# MiiScoreBoard.net
KiCad netlist of a schematic drawn in EAGLE
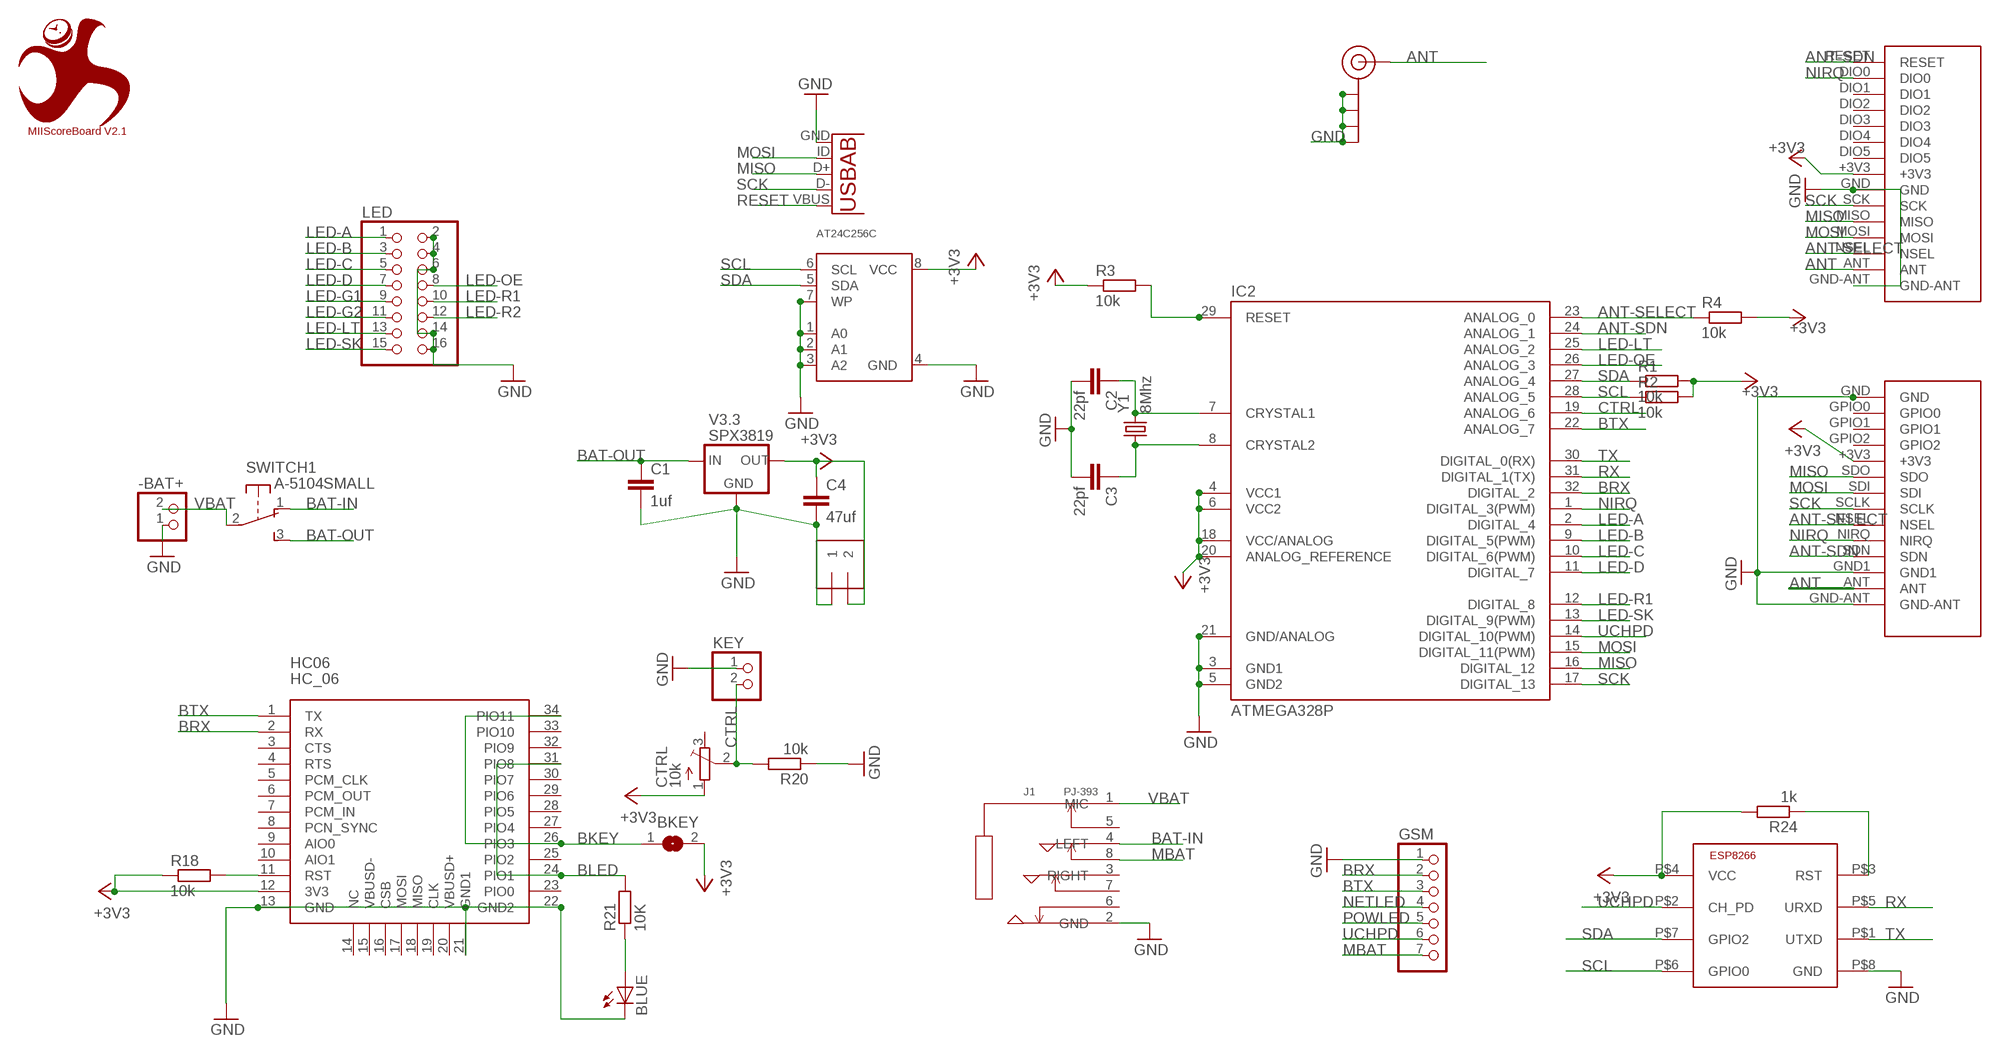
[diagram p0: schematic, sheet 1]

(export (version "E")
  (design (tool "Eeschema 10.0.6"))
  (components
    (comp (ref "-BAT+")
      (value "JST_2PIN-THM")
      (footprint "eagle-import:JST-PH-2-THM")
      (libsource (lib "eagle-import") (part "JST_2PIN-THM"))
    )
    (comp (ref "-LED+")
      (value "-BAT+")
      (footprint "eagle-import:1X2-3.5MM")
      (libsource (lib "eagle-import") (part "1X2-3.5MM"))
    )
    (comp (ref "AT24C256C")
      (value "EEPROM_I2C_SOIC8_GENERIC")
      (footprint "eagle-import:SOIC8_150MIL")
      (libsource (lib "eagle-import") (part "EEPROM_I2C_SOIC8_GENERIC"))
    )
    (comp (ref "BKEY")
      (value "SOLDERJUMPER")
      (footprint "eagle-import:SOLDERJUMPER_ARROW_NOPASTE")
      (libsource (lib "eagle-import") (part "SOLDERJUMPER"))
    )
    (comp (ref "BLUE")
      (value "LEDCHIP-LED0805")
      (footprint "eagle-import:CHIP-LED0805")
      (libsource (lib "eagle-import") (part "LEDCHIP-LED0805"))
    )
    (comp (ref "C1")
      (value "1uf")
      (footprint "eagle-import:C0805")
      (libsource (lib "eagle-import") (part "C-EUC0805"))
    )
    (comp (ref "C2")
      (value "22pf")
      (footprint "eagle-import:C0805")
      (libsource (lib "eagle-import") (part "C-EUC0805"))
    )
    (comp (ref "C3")
      (value "22pf")
      (footprint "eagle-import:C0805")
      (libsource (lib "eagle-import") (part "C-EUC0805"))
    )
    (comp (ref "C4")
      (value "47uf")
      (footprint "eagle-import:C0805")
      (libsource (lib "eagle-import") (part "C-EUC0805"))
    )
    (comp (ref "CTRL")
      (value "10k")
      (footprint "eagle-import:TC33X")
      (libsource (lib "eagle-import") (part "TRIMPOTTC33X"))
    )
    (comp (ref "GSM")
      (value "PINHD-1X07_2.54")
      (footprint "eagle-import:1X07")
      (libsource (lib "eagle-import") (part "PINHD-1X07_2.54"))
    )
    (comp (ref "HC06")
      (value "HC_06")
      (footprint "eagle-import:BLUETOOTH_SMD")
      (libsource (lib "eagle-import") (part "HC_05"))
    )
    (comp (ref "IC2")
      (value "ATMEGA328P")
      (footprint "eagle-import:TQFP32-08")
      (libsource (lib "eagle-import") (part "ATMEGA168-AU"))
    )
    (comp (ref "ISP1")
      (value "USB-ABUSB_SIERK")
      (footprint "eagle-import:USB_AB_MICRO_SJH")
      (libsource (lib "eagle-import") (part "USB-ABUSB_SIERK"))
    )
    (comp (ref "J$1")
      (value "SMA_EDGE")
      (footprint "eagle-import:SMA-EDGE")
      (libsource (lib "eagle-import") (part "SMA_EDGE"))
    )
    (comp (ref "J1")
      (value "PJ-393")
      (footprint "eagle-import:AUDIO8P-SMD-3.5-14.5X6.1X4.0MM")
      (libsource (lib "eagle-import") (part "AUDIO-JACK-PJ-393(8P-SMD)"))
    )
    (comp (ref "KEY")
      (value "PINHD-1X02_2.54-90°")
      (footprint "eagle-import:1X02_90")
      (libsource (lib "eagle-import") (part "PINHD-1X02_2.54-90°"))
    )
    (comp (ref "LED")
      (value "PINHD-2X08_2.54")
      (footprint "eagle-import:2X08")
      (libsource (lib "eagle-import") (part "PINHD-2X08_2.54"))
    )
    (comp (ref "R1")
      (value "10k")
      (footprint "eagle-import:R0805")
      (libsource (lib "eagle-import") (part "R-EU_R0805"))
    )
    (comp (ref "R2")
      (value "10k")
      (footprint "eagle-import:R0805")
      (libsource (lib "eagle-import") (part "R-EU_R0805"))
    )
    (comp (ref "R3")
      (value "10k")
      (footprint "eagle-import:R0805")
      (libsource (lib "eagle-import") (part "R-EU_R0805"))
    )
    (comp (ref "R4")
      (value "10k")
      (footprint "eagle-import:R0805")
      (libsource (lib "eagle-import") (part "R-EU_R0805"))
    )
    (comp (ref "R18")
      (value "10k")
      (footprint "eagle-import:R0805")
      (libsource (lib "eagle-import") (part "R-EU_R0805"))
    )
    (comp (ref "R20")
      (value "10k")
      (footprint "eagle-import:R0805")
      (libsource (lib "eagle-import") (part "R-EU_R0805"))
    )
    (comp (ref "R21")
      (value "10K")
      (footprint "eagle-import:R0805")
      (libsource (lib "eagle-import") (part "R-EU_R0805"))
    )
    (comp (ref "R24")
      (value "1k")
      (footprint "eagle-import:R0805")
      (libsource (lib "eagle-import") (part "R-EU_R0805"))
    )
    (comp (ref "SWITCH")
      (value "A-5104SMALL")
      (footprint "eagle-import:A-5104-SMALL")
      (libsource (lib "eagle-import") (part "A-5104SMALL"))
    )
    (comp (ref "U$1")
      (value "MIIScoreBoard V2.1")
      (footprint "eagle-import:MIICHRONO")
      (libsource (lib "eagle-import") (part "MIICHRONO"))
    )
    (comp (ref "U$2")
      (value "DRF1278F")
      (footprint "eagle-import:DRF1278F")
      (libsource (lib "eagle-import") (part "DRF1278F"))
    )
    (comp (ref "U$6")
      (value "ESP8266-01")
      (footprint "eagle-import:ESP-01")
      (libsource (lib "eagle-import") (part "ESP8266-01"))
    )
    (comp (ref "U$7")
      (value "SI4432")
      (footprint "eagle-import:SI4432")
      (libsource (lib "eagle-import") (part "SPI4432"))
    )
    (comp (ref "V3.3")
      (value "SPX3819")
      (footprint "eagle-import:SOT23-5")
      (libsource (lib "eagle-import") (part "SPX3819"))
    )
    (comp (ref "Y1")
      (value "8Mhz")
      (footprint "eagle-import:HC49UP")
      (libsource (lib "eagle-import") (part "CRYSTALSMD"))
    )
  )
  (nets
    (net (code "1") (name "+3V3") (class "Default")
      (node (ref "-LED+") (pin "2") (pinfunction "2_2") (pintype "passive"))
      (node (ref "AT24C256C") (pin "8") (pinfunction "VCC_8") (pintype "power_in"))
      (node (ref "BKEY") (pin "2") (pinfunction "2_2") (pintype "passive"))
      (node (ref "C4") (pin "1") (pinfunction "1_1") (pintype "passive"))
      (node (ref "CTRL") (pin "1") (pinfunction "A_1") (pintype "passive"))
      (node (ref "HC06") (pin "12") (pinfunction "3V3_12") (pintype "bidirectional"))
      (node (ref "IC2") (pin "18") (pinfunction "VCC/ANALOG_18") (pintype "passive"))
      (node (ref "IC2") (pin "20") (pinfunction "ANALOG_REFERENCE_20") (pintype "passive"))
      (node (ref "IC2") (pin "4") (pinfunction "VCC1_4") (pintype "power_in"))
      (node (ref "IC2") (pin "6") (pinfunction "VCC2_6") (pintype "power_in"))
      (node (ref "R1") (pin "2") (pinfunction "2_2") (pintype "passive"))
      (node (ref "R18") (pin "1") (pinfunction "1_1") (pintype "passive"))
      (node (ref "R2") (pin "2") (pinfunction "2_2") (pintype "passive"))
      (node (ref "R24") (pin "2") (pinfunction "2_2") (pintype "passive"))
      (node (ref "R3") (pin "1") (pinfunction "1_1") (pintype "passive"))
      (node (ref "R4") (pin "2") (pinfunction "2_2") (pintype "passive"))
      (node (ref "U$2") (pin "+3V3") (pinfunction "+3V3_+3V3") (pintype "bidirectional"))
      (node (ref "U$6") (pin "P$4") (pinfunction "VCC_P$4") (pintype "bidirectional"))
      (node (ref "U$7") (pin "+3V3") (pinfunction "+3V3_+3V3") (pintype "bidirectional"))
      (node (ref "V3.3") (pin "5") (pinfunction "OUT_5") (pintype "output"))
    )
    (net (code "2") (name "/ANT") (class "Default")
      (node (ref "J$1") (pin "$P1") (pinfunction "SIGNAL_$P1") (pintype "bidirectional"))
      (node (ref "U$2") (pin "ANT") (pinfunction "ANT_ANT") (pintype "bidirectional"))
      (node (ref "U$7") (pin "ANT") (pinfunction "ANT_ANT") (pintype "bidirectional"))
    )
    (net (code "3") (name "/ANT-SDN") (class "Default")
      (node (ref "IC2") (pin "24") (pinfunction "ANALOG_1_24") (pintype "bidirectional"))
      (node (ref "U$2") (pin "RESET") (pinfunction "RESET_RESET") (pintype "bidirectional"))
      (node (ref "U$7") (pin "SDN") (pinfunction "SDN_SDN") (pintype "bidirectional"))
    )
    (net (code "4") (name "/ANT-SELECT") (class "Default")
      (node (ref "IC2") (pin "23") (pinfunction "ANALOG_0_23") (pintype "bidirectional"))
      (node (ref "R4") (pin "1") (pinfunction "1_1") (pintype "passive"))
      (node (ref "U$2") (pin "NSEL") (pinfunction "NSEL_NSEL") (pintype "bidirectional"))
      (node (ref "U$7") (pin "NSEL") (pinfunction "NSEL_NSEL") (pintype "bidirectional"))
    )
    (net (code "5") (name "/BAT-IN") (class "Default")
      (node (ref "J1") (pin "4") (pinfunction "LEFT_4") (pintype "bidirectional"))
      (node (ref "SWITCH") (pin "1") (pinfunction "O_1") (pintype "passive"))
    )
    (net (code "6") (name "/BAT-OUT") (class "Default")
      (node (ref "C1") (pin "1") (pinfunction "1_1") (pintype "passive"))
      (node (ref "SWITCH") (pin "3") (pinfunction "S_3") (pintype "passive"))
      (node (ref "V3.3") (pin "1") (pinfunction "IN_1") (pintype "input"))
      (node (ref "V3.3") (pin "3") (pinfunction "IN_3") (pintype "input"))
    )
    (net (code "7") (name "/BKEY") (class "Default")
      (node (ref "BKEY") (pin "1") (pinfunction "1_1") (pintype "passive"))
      (node (ref "HC06") (pin "26") (pinfunction "PIO3_26") (pintype "bidirectional"))
      (node (ref "HC06") (pin "34") (pinfunction "PIO11_34") (pintype "bidirectional"))
    )
    (net (code "8") (name "/BLED") (class "Default")
      (node (ref "HC06") (pin "24") (pinfunction "PIO1_24") (pintype "bidirectional"))
      (node (ref "HC06") (pin "31") (pinfunction "PIO8_31") (pintype "bidirectional"))
      (node (ref "R21") (pin "2") (pinfunction "2_2") (pintype "passive"))
    )
    (net (code "9") (name "/BRX") (class "Default")
      (node (ref "GSM") (pin "2") (pinfunction "2_2") (pintype "passive"))
      (node (ref "HC06") (pin "2") (pinfunction "RX_2") (pintype "bidirectional"))
      (node (ref "IC2") (pin "32") (pinfunction "DIGITAL_2_32") (pintype "bidirectional"))
    )
    (net (code "10") (name "/BTX") (class "Default")
      (node (ref "GSM") (pin "3") (pinfunction "3_3") (pintype "passive"))
      (node (ref "HC06") (pin "1") (pinfunction "TX_1") (pintype "bidirectional"))
      (node (ref "IC2") (pin "22") (pinfunction "ANALOG_7_22") (pintype "passive"))
    )
    (net (code "11") (name "/CTRL") (class "Default")
      (node (ref "CTRL") (pin "2") (pinfunction "S_2") (pintype "passive"))
      (node (ref "IC2") (pin "19") (pinfunction "ANALOG_6_19") (pintype "passive"))
      (node (ref "KEY") (pin "2") (pinfunction "2_2") (pintype "passive"))
      (node (ref "R20") (pin "2") (pinfunction "2_2") (pintype "passive"))
    )
    (net (code "12") (name "/LED-A") (class "Default")
      (node (ref "IC2") (pin "2") (pinfunction "DIGITAL_4_2") (pintype "bidirectional"))
      (node (ref "LED") (pin "1") (pinfunction "1_1") (pintype "passive"))
    )
    (net (code "13") (name "/LED-B") (class "Default")
      (node (ref "IC2") (pin "9") (pinfunction "DIGITAL_5(PWM)_9") (pintype "bidirectional"))
      (node (ref "LED") (pin "3") (pinfunction "3_3") (pintype "passive"))
    )
    (net (code "14") (name "/LED-C") (class "Default")
      (node (ref "IC2") (pin "10") (pinfunction "DIGITAL_6(PWM)_10") (pintype "bidirectional"))
      (node (ref "LED") (pin "5") (pinfunction "5_5") (pintype "passive"))
    )
    (net (code "15") (name "/LED-D") (class "Default")
      (node (ref "IC2") (pin "11") (pinfunction "DIGITAL_7_11") (pintype "bidirectional"))
      (node (ref "LED") (pin "7") (pinfunction "7_7") (pintype "passive"))
    )
    (net (code "16") (name "/LED-G1") (class "Default")
      (node (ref "LED") (pin "9") (pinfunction "9_9") (pintype "passive"))
    )
    (net (code "17") (name "/LED-G2") (class "Default")
      (node (ref "LED") (pin "11") (pinfunction "11_11") (pintype "passive"))
    )
    (net (code "18") (name "/LED-LT") (class "Default")
      (node (ref "IC2") (pin "25") (pinfunction "ANALOG_2_25") (pintype "bidirectional"))
      (node (ref "LED") (pin "13") (pinfunction "13_13") (pintype "passive"))
    )
    (net (code "19") (name "/LED-OE") (class "Default")
      (node (ref "IC2") (pin "26") (pinfunction "ANALOG_3_26") (pintype "bidirectional"))
      (node (ref "LED") (pin "8") (pinfunction "8_8") (pintype "passive"))
    )
    (net (code "20") (name "/LED-R1") (class "Default")
      (node (ref "IC2") (pin "12") (pinfunction "DIGITAL_8_12") (pintype "bidirectional"))
      (node (ref "LED") (pin "10") (pinfunction "10_10") (pintype "passive"))
    )
    (net (code "21") (name "/LED-R2") (class "Default")
      (node (ref "LED") (pin "12") (pinfunction "12_12") (pintype "passive"))
    )
    (net (code "22") (name "/LED-SK") (class "Default")
      (node (ref "IC2") (pin "13") (pinfunction "DIGITAL_9(PWM)_13") (pintype "bidirectional"))
      (node (ref "LED") (pin "15") (pinfunction "15_15") (pintype "passive"))
    )
    (net (code "23") (name "/MBAT") (class "Default")
      (node (ref "GSM") (pin "7") (pinfunction "7_7") (pintype "passive"))
      (node (ref "J1") (pin "8") (pinfunction "8_8") (pintype "bidirectional"))
    )
    (net (code "24") (name "/MISO") (class "Default")
      (node (ref "IC2") (pin "16") (pinfunction "DIGITAL_12_16") (pintype "bidirectional"))
      (node (ref "ISP1") (pin "D+") (pinfunction "D+_D+") (pintype "bidirectional"))
      (node (ref "U$2") (pin "MISO") (pinfunction "MISO_MISO") (pintype "bidirectional"))
      (node (ref "U$7") (pin "SDO") (pinfunction "SDO_SDO") (pintype "bidirectional"))
    )
    (net (code "25") (name "/MOSI") (class "Default")
      (node (ref "IC2") (pin "15") (pinfunction "DIGITAL_11(PWM)_15") (pintype "bidirectional"))
      (node (ref "ISP1") (pin "ID") (pinfunction "USBID_ID") (pintype "bidirectional"))
      (node (ref "U$2") (pin "MOSI") (pinfunction "MOSI_MOSI") (pintype "bidirectional"))
      (node (ref "U$7") (pin "SDI") (pinfunction "SDI_SDI") (pintype "bidirectional"))
    )
    (net (code "26") (name "/NETLED") (class "Default")
      (node (ref "GSM") (pin "4") (pinfunction "4_4") (pintype "passive"))
    )
    (net (code "27") (name "/NIRQ") (class "Default")
      (node (ref "IC2") (pin "1") (pinfunction "DIGITAL_3(PWM)_1") (pintype "bidirectional"))
      (node (ref "U$2") (pin "DIO0") (pinfunction "DIO0_DIO0") (pintype "bidirectional"))
      (node (ref "U$7") (pin "NIRQ") (pinfunction "NIRQ_NIRQ") (pintype "bidirectional"))
    )
    (net (code "28") (name "/POWLED") (class "Default")
      (node (ref "GSM") (pin "5") (pinfunction "5_5") (pintype "passive"))
    )
    (net (code "29") (name "/RESET") (class "Default")
      (node (ref "IC2") (pin "29") (pinfunction "RESET_29") (pintype "bidirectional"))
      (node (ref "ISP1") (pin "VBUS") (pinfunction "VBUS_VBUS") (pintype "bidirectional"))
      (node (ref "R3") (pin "2") (pinfunction "2_2") (pintype "passive"))
    )
    (net (code "30") (name "/RX") (class "Default")
      (node (ref "IC2") (pin "31") (pinfunction "DIGITAL_1(TX)_31") (pintype "bidirectional"))
      (node (ref "U$6") (pin "P$5") (pinfunction "URXD_P$5") (pintype "bidirectional"))
    )
    (net (code "31") (name "/SCK") (class "Default")
      (node (ref "IC2") (pin "17") (pinfunction "DIGITAL_13_17") (pintype "bidirectional"))
      (node (ref "ISP1") (pin "D-") (pinfunction "D-_D-") (pintype "bidirectional"))
      (node (ref "U$2") (pin "SCK") (pinfunction "SCK_SCK") (pintype "bidirectional"))
      (node (ref "U$7") (pin "SCLK") (pinfunction "SCLK_SCLK") (pintype "bidirectional"))
    )
    (net (code "32") (name "/SCL") (class "Default")
      (node (ref "AT24C256C") (pin "6") (pinfunction "SCL_6") (pintype "input"))
      (node (ref "IC2") (pin "28") (pinfunction "ANALOG_5_28") (pintype "bidirectional"))
      (node (ref "R2") (pin "1") (pinfunction "1_1") (pintype "passive"))
      (node (ref "U$6") (pin "P$6") (pinfunction "GPIO0_P$6") (pintype "bidirectional"))
    )
    (net (code "33") (name "/SDA") (class "Default")
      (node (ref "AT24C256C") (pin "5") (pinfunction "SDA_5") (pintype "bidirectional"))
      (node (ref "IC2") (pin "27") (pinfunction "ANALOG_4_27") (pintype "bidirectional"))
      (node (ref "R1") (pin "1") (pinfunction "1_1") (pintype "passive"))
      (node (ref "U$6") (pin "P$7") (pinfunction "GPIO2_P$7") (pintype "bidirectional"))
    )
    (net (code "34") (name "/TX") (class "Default")
      (node (ref "IC2") (pin "30") (pinfunction "DIGITAL_0(RX)_30") (pintype "bidirectional"))
      (node (ref "U$6") (pin "P$1") (pinfunction "UTXD_P$1") (pintype "bidirectional"))
    )
    (net (code "35") (name "/UCHPD") (class "Default")
      (node (ref "GSM") (pin "6") (pinfunction "6_6") (pintype "passive"))
      (node (ref "IC2") (pin "14") (pinfunction "DIGITAL_10(PWM)_14") (pintype "bidirectional"))
      (node (ref "U$6") (pin "P$2") (pinfunction "CH_PD_P$2") (pintype "bidirectional"))
    )
    (net (code "36") (name "/VBAT") (class "Default")
      (node (ref "-BAT+") (pin "2") (pinfunction "1_2") (pintype "passive"))
      (node (ref "J1") (pin "1") (pinfunction "MIC_1") (pintype "bidirectional"))
      (node (ref "SWITCH") (pin "2") (pinfunction "P_2") (pintype "passive"))
    )
    (net (code "37") (name "GND") (class "Default")
      (node (ref "-BAT+") (pin "1") (pinfunction "2_1") (pintype "passive"))
      (node (ref "-LED+") (pin "1") (pinfunction "1_1") (pintype "passive"))
      (node (ref "AT24C256C") (pin "1") (pinfunction "A0_1") (pintype "input"))
      (node (ref "AT24C256C") (pin "2") (pinfunction "A1_2") (pintype "input"))
      (node (ref "AT24C256C") (pin "3") (pinfunction "A2_3") (pintype "input"))
      (node (ref "AT24C256C") (pin "4") (pinfunction "GND_4") (pintype "power_in"))
      (node (ref "AT24C256C") (pin "7") (pinfunction "WP_7") (pintype "input"))
      (node (ref "BLUE") (pin "C") (pinfunction "C_C") (pintype "passive"))
      (node (ref "C1") (pin "2") (pinfunction "2_2") (pintype "passive"))
      (node (ref "C2") (pin "2") (pinfunction "2_2") (pintype "passive"))
      (node (ref "C3") (pin "2") (pinfunction "2_2") (pintype "passive"))
      (node (ref "C4") (pin "2") (pinfunction "2_2") (pintype "passive"))
      (node (ref "GSM") (pin "1") (pinfunction "1_1") (pintype "passive"))
      (node (ref "HC06") (pin "13") (pinfunction "GND_13") (pintype "bidirectional"))
      (node (ref "HC06") (pin "21") (pinfunction "GND1_21") (pintype "bidirectional"))
      (node (ref "HC06") (pin "22") (pinfunction "GND2_22") (pintype "bidirectional"))
      (node (ref "IC2") (pin "21") (pinfunction "GND/ANALOG_21") (pintype "power_in"))
      (node (ref "IC2") (pin "3") (pinfunction "GND1_3") (pintype "power_in"))
      (node (ref "IC2") (pin "5") (pinfunction "GND2_5") (pintype "power_in"))
      (node (ref "ISP1") (pin "GND") (pinfunction "GND_GND") (pintype "bidirectional"))
      (node (ref "J$1") (pin "GND@0") (pinfunction "GND_GND@0") (pintype "bidirectional"))
      (node (ref "J$1") (pin "GND@1") (pinfunction "GND_GND@1") (pintype "bidirectional"))
      (node (ref "J$1") (pin "GND@2") (pinfunction "GND_GND@2") (pintype "bidirectional"))
      (node (ref "J$1") (pin "GND@3") (pinfunction "GND_GND@3") (pintype "bidirectional"))
      (node (ref "J1") (pin "2") (pinfunction "GND_2") (pintype "bidirectional"))
      (node (ref "KEY") (pin "1") (pinfunction "1_1") (pintype "passive"))
      (node (ref "LED") (pin "14") (pinfunction "14_14") (pintype "passive"))
      (node (ref "LED") (pin "16") (pinfunction "16_16") (pintype "passive"))
      (node (ref "LED") (pin "2") (pinfunction "2_2") (pintype "passive"))
      (node (ref "LED") (pin "4") (pinfunction "4_4") (pintype "passive"))
      (node (ref "LED") (pin "6") (pinfunction "6_6") (pintype "passive"))
      (node (ref "R20") (pin "1") (pinfunction "1_1") (pintype "passive"))
      (node (ref "U$2") (pin "GND") (pinfunction "GND_GND") (pintype "bidirectional"))
      (node (ref "U$2") (pin "GND-ANT") (pinfunction "GND-ANT_GND-ANT") (pintype "bidirectional"))
      (node (ref "U$6") (pin "P$8") (pinfunction "GND_P$8") (pintype "bidirectional"))
      (node (ref "U$7") (pin "GND") (pinfunction "GND_GND") (pintype "bidirectional"))
      (node (ref "U$7") (pin "GND-ANT") (pinfunction "GND-ANT_GND-ANT") (pintype "bidirectional"))
      (node (ref "U$7") (pin "GND1") (pinfunction "GND1_GND1") (pintype "bidirectional"))
      (node (ref "V3.3") (pin "2") (pinfunction "GND_2") (pintype "input"))
    )
    (net (code "38") (name "Net-(BLUE-PadA)") (class "Default")
      (node (ref "BLUE") (pin "A") (pinfunction "A_A") (pintype "passive"))
      (node (ref "R21") (pin "1") (pinfunction "1_1") (pintype "passive"))
    )
    (net (code "39") (name "Net-(HC06-RST)") (class "Default")
      (node (ref "HC06") (pin "11") (pinfunction "RST_11") (pintype "bidirectional"))
      (node (ref "R18") (pin "2") (pinfunction "2_2") (pintype "passive"))
    )
    (net (code "40") (name "Net-(IC2-CRYSTAL1)") (class "Default")
      (node (ref "C2") (pin "1") (pinfunction "1_1") (pintype "passive"))
      (node (ref "IC2") (pin "7") (pinfunction "CRYSTAL1_7") (pintype "bidirectional"))
      (node (ref "Y1") (pin "2") (pinfunction "2_2") (pintype "passive"))
    )
    (net (code "41") (name "Net-(IC2-CRYSTAL2)") (class "Default")
      (node (ref "C3") (pin "1") (pinfunction "1_1") (pintype "passive"))
      (node (ref "IC2") (pin "8") (pinfunction "CRYSTAL2_8") (pintype "bidirectional"))
      (node (ref "Y1") (pin "1") (pinfunction "1_1") (pintype "passive"))
    )
    (net (code "42") (name "Net-(U$6-RST)") (class "Default")
      (node (ref "R24") (pin "1") (pinfunction "1_1") (pintype "passive"))
      (node (ref "U$6") (pin "P$3") (pinfunction "RST_P$3") (pintype "bidirectional"))
    )
    (net (code "43") (name "unconnected-(CTRL-E-Pad3)") (class "Default")
      (node (ref "CTRL") (pin "3") (pinfunction "E_3") (pintype "passive"))
    )
    (net (code "44") (name "unconnected-(HC06-AIO0-Pad9)") (class "Default")
      (node (ref "HC06") (pin "9") (pinfunction "AIO0_9") (pintype "bidirectional"))
    )
    (net (code "45") (name "unconnected-(HC06-AIO1-Pad10)") (class "Default")
      (node (ref "HC06") (pin "10") (pinfunction "AIO1_10") (pintype "bidirectional"))
    )
    (net (code "46") (name "unconnected-(HC06-CLK-Pad19)") (class "Default")
      (node (ref "HC06") (pin "19") (pinfunction "CLK_19") (pintype "bidirectional"))
    )
    (net (code "47") (name "unconnected-(HC06-CSB-Pad16)") (class "Default")
      (node (ref "HC06") (pin "16") (pinfunction "CSB_16") (pintype "bidirectional"))
    )
    (net (code "48") (name "unconnected-(HC06-CTS-Pad3)") (class "Default")
      (node (ref "HC06") (pin "3") (pinfunction "CTS_3") (pintype "bidirectional"))
    )
    (net (code "49") (name "unconnected-(HC06-MISO-Pad18)") (class "Default")
      (node (ref "HC06") (pin "18") (pinfunction "MISO_18") (pintype "bidirectional"))
    )
    (net (code "50") (name "unconnected-(HC06-MOSI-Pad17)") (class "Default")
      (node (ref "HC06") (pin "17") (pinfunction "MOSI_17") (pintype "bidirectional"))
    )
    (net (code "51") (name "unconnected-(HC06-NC-Pad14)") (class "Default")
      (node (ref "HC06") (pin "14") (pinfunction "NC_14") (pintype "bidirectional"))
    )
    (net (code "52") (name "unconnected-(HC06-PCM_CLK-Pad5)") (class "Default")
      (node (ref "HC06") (pin "5") (pinfunction "PCM_CLK_5") (pintype "bidirectional"))
    )
    (net (code "53") (name "unconnected-(HC06-PCM_IN-Pad7)") (class "Default")
      (node (ref "HC06") (pin "7") (pinfunction "PCM_IN_7") (pintype "bidirectional"))
    )
    (net (code "54") (name "unconnected-(HC06-PCM_OUT-Pad6)") (class "Default")
      (node (ref "HC06") (pin "6") (pinfunction "PCM_OUT_6") (pintype "bidirectional"))
    )
    (net (code "55") (name "unconnected-(HC06-PCN_SYNC-Pad8)") (class "Default")
      (node (ref "HC06") (pin "8") (pinfunction "PCN_SYNC_8") (pintype "bidirectional"))
    )
    (net (code "56") (name "unconnected-(HC06-PIO0-Pad23)") (class "Default")
      (node (ref "HC06") (pin "23") (pinfunction "PIO0_23") (pintype "bidirectional"))
    )
    (net (code "57") (name "unconnected-(HC06-PIO2-Pad25)") (class "Default")
      (node (ref "HC06") (pin "25") (pinfunction "PIO2_25") (pintype "bidirectional"))
    )
    (net (code "58") (name "unconnected-(HC06-PIO4-Pad27)") (class "Default")
      (node (ref "HC06") (pin "27") (pinfunction "PIO4_27") (pintype "bidirectional"))
    )
    (net (code "59") (name "unconnected-(HC06-PIO5-Pad28)") (class "Default")
      (node (ref "HC06") (pin "28") (pinfunction "PIO5_28") (pintype "bidirectional"))
    )
    (net (code "60") (name "unconnected-(HC06-PIO6-Pad29)") (class "Default")
      (node (ref "HC06") (pin "29") (pinfunction "PIO6_29") (pintype "bidirectional"))
    )
    (net (code "61") (name "unconnected-(HC06-PIO7-Pad30)") (class "Default")
      (node (ref "HC06") (pin "30") (pinfunction "PIO7_30") (pintype "bidirectional"))
    )
    (net (code "62") (name "unconnected-(HC06-PIO9-Pad32)") (class "Default")
      (node (ref "HC06") (pin "32") (pinfunction "PIO9_32") (pintype "bidirectional"))
    )
    (net (code "63") (name "unconnected-(HC06-PIO10-Pad33)") (class "Default")
      (node (ref "HC06") (pin "33") (pinfunction "PIO10_33") (pintype "bidirectional"))
    )
    (net (code "64") (name "unconnected-(HC06-RTS-Pad4)") (class "Default")
      (node (ref "HC06") (pin "4") (pinfunction "RTS_4") (pintype "bidirectional"))
    )
    (net (code "65") (name "unconnected-(HC06-VBUSD+-Pad20)") (class "Default")
      (node (ref "HC06") (pin "20") (pinfunction "VBUSD+_20") (pintype "bidirectional"))
    )
    (net (code "66") (name "unconnected-(HC06-VBUSD--Pad15)") (class "Default")
      (node (ref "HC06") (pin "15") (pinfunction "VBUSD-_15") (pintype "bidirectional"))
    )
    (net (code "67") (name "unconnected-(J1-Pad5)") (class "Default")
      (node (ref "J1") (pin "5") (pinfunction "5_5") (pintype "bidirectional"))
    )
    (net (code "68") (name "unconnected-(J1-Pad6)") (class "Default")
      (node (ref "J1") (pin "6") (pinfunction "6_6") (pintype "bidirectional"))
    )
    (net (code "69") (name "unconnected-(J1-Pad7)") (class "Default")
      (node (ref "J1") (pin "7") (pinfunction "7_7") (pintype "bidirectional"))
    )
    (net (code "70") (name "unconnected-(J1-RIGHT-Pad3)") (class "Default")
      (node (ref "J1") (pin "3") (pinfunction "RIGHT_3") (pintype "bidirectional"))
    )
    (net (code "71") (name "unconnected-(U$2-PadDIO1)") (class "Default")
      (node (ref "U$2") (pin "DIO1") (pinfunction "DIO1_DIO1") (pintype "bidirectional"))
    )
    (net (code "72") (name "unconnected-(U$2-PadDIO2)") (class "Default")
      (node (ref "U$2") (pin "DIO2") (pinfunction "DIO2_DIO2") (pintype "bidirectional"))
    )
    (net (code "73") (name "unconnected-(U$2-PadDIO3)") (class "Default")
      (node (ref "U$2") (pin "DIO3") (pinfunction "DIO3_DIO3") (pintype "bidirectional"))
    )
    (net (code "74") (name "unconnected-(U$2-PadDIO4)") (class "Default")
      (node (ref "U$2") (pin "DIO4") (pinfunction "DIO4_DIO4") (pintype "bidirectional"))
    )
    (net (code "75") (name "unconnected-(U$2-PadDIO5)") (class "Default")
      (node (ref "U$2") (pin "DIO5") (pinfunction "DIO5_DIO5") (pintype "bidirectional"))
    )
    (net (code "76") (name "unconnected-(U$7-PadGPIO0)") (class "Default")
      (node (ref "U$7") (pin "GPIO0") (pinfunction "GPIO0_GPIO0") (pintype "bidirectional"))
    )
    (net (code "77") (name "unconnected-(U$7-PadGPIO1)") (class "Default")
      (node (ref "U$7") (pin "GPIO1") (pinfunction "GPIO1_GPIO1") (pintype "bidirectional"))
    )
    (net (code "78") (name "unconnected-(U$7-PadGPIO2)") (class "Default")
      (node (ref "U$7") (pin "GPIO2") (pinfunction "GPIO2_GPIO2") (pintype "bidirectional"))
    )
  )
)
